# Power_Supply.net
KiCad netlist of a schematic drawn in Altium Designer
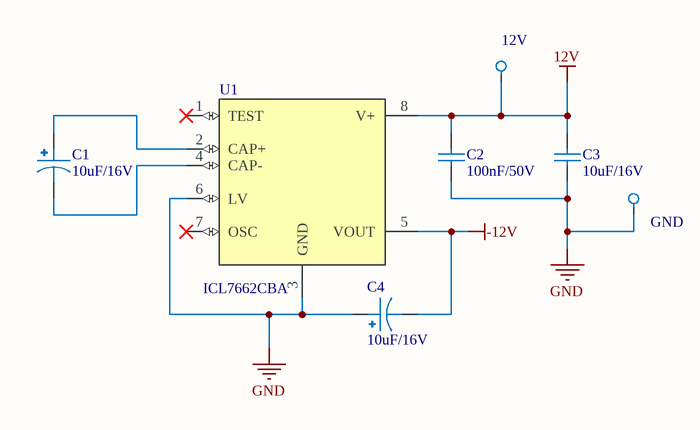
[diagram p0: Power_Supply.SchDoc]

(export (version "E")
  (design (tool "Eeschema 10.0.6"))
  (components
    (comp (ref "12V")
      (value "Testpoint_SMD")
      (footprint "TestPoint_Pad_3.0x3.0mm")
      (libsource (lib "BluetoothTracking") (part "Testpoint_SMD"))
    )
    (comp (ref "C1")
      (value "10uF/16V")
      (footprint "TanTa_Cap_A")
      (description "Tantalum Capacitors 10uF 16V 1206")
      (fields (field (name "SUPPLY PART NUMBER") "AVX"))
      (libsource (lib "") (part "Tanta_Cap_10uF_16V_1206_1"))
    )
    (comp (ref "C2")
      (value "100nF/50V")
      (footprint "CAP_0603")
      (description "CAP, size 0603, 100nF, 50V")
      (fields (field (name "SUPPLY PART NUMBER") "Tụ Gốm 0603 100nF (0.1uF) 50V"))
      (libsource (lib "BluetoothTracking") (part "Ceramic_Cap_100nF_50V_0603"))
    )
    (comp (ref "C3")
      (value "10uF/16V")
      (footprint "CAP_0603")
      (description "CAP, size 0603, 10uF, 16V")
      (fields (field (name "SUPPLY PART NUMBER") "Tụ Gốm 0603 10uF 16V"))
      (libsource (lib "BluetoothTracking") (part "Ceramic_Cap_10uF_16V_0603"))
    )
    (comp (ref "C4")
      (value "10uF/16V")
      (footprint "TanTa_Cap_A")
      (description "Tantalum Capacitors 10uF 16V 1206")
      (fields (field (name "SUPPLY PART NUMBER") "AVX"))
      (libsource (lib "BluetoothTracking") (part "Tanta_Cap_10uF_16V_1206"))
    )
    (comp (ref "GND")
      (value "Testpoint_SMD")
      (footprint "TestPoint_Pad_3.0x3.0mm")
      (libsource (lib "BluetoothTracking") (part "Testpoint_SMD"))
    )
    (comp (ref "U1")
      (value "ICL7662CBA")
      (footprint "SOIC-8")
      (description "Vin: 4.5V ~ 20V, Vout: -Vin, 8-SOIC")
      (fields (field (name "SUPPLY PART NUMBER") "IC Dán ICL7662"))
      (libsource (lib "BluetoothTracking") (part "ICL7662CBA"))
    )
  )
  (nets
    (net (code "1") (name "-12V") (class "Default")
      (node (ref "C4") (pin "2") (pinfunction "2_2") (pintype "passive"))
      (node (ref "U1") (pin "5") (pinfunction "VOUT_5") (pintype "power_in"))
    )
    (net (code "2") (name "12V") (class "Default")
      (node (ref "12V") (pin "1") (pinfunction "1_1") (pintype "passive"))
      (node (ref "C2") (pin "2") (pinfunction "2_2") (pintype "passive"))
      (node (ref "C3") (pin "2") (pinfunction "2_2") (pintype "passive"))
      (node (ref "U1") (pin "8") (pinfunction "V+_8") (pintype "power_in"))
    )
    (net (code "3") (name "GND") (class "Default")
      (node (ref "C2") (pin "1") (pinfunction "1_1") (pintype "passive"))
      (node (ref "C3") (pin "1") (pinfunction "1_1") (pintype "passive"))
      (node (ref "C4") (pin "1") (pinfunction "1_1") (pintype "passive"))
      (node (ref "GND") (pin "1") (pinfunction "1_1") (pintype "passive"))
      (node (ref "U1") (pin "3") (pinfunction "GND_3") (pintype "power_in"))
      (node (ref "U1") (pin "6") (pinfunction "LV_6") (pintype "bidirectional"))
    )
    (net (code "4") (name "Net-(U1-CAP+)") (class "Default")
      (node (ref "C1") (pin "1") (pinfunction "1_1") (pintype "passive"))
      (node (ref "U1") (pin "2") (pinfunction "CAP+_2") (pintype "bidirectional"))
    )
    (net (code "5") (name "Net-(U1-CAP-)") (class "Default")
      (node (ref "C1") (pin "2") (pinfunction "2_2") (pintype "passive"))
      (node (ref "U1") (pin "4") (pinfunction "CAP-_4") (pintype "bidirectional"))
    )
    (net (code "6") (name "unconnected-(U1-OSC-Pad7)") (class "Default")
      (node (ref "U1") (pin "7") (pinfunction "OSC_7") (pintype "bidirectional+no_connect"))
    )
    (net (code "7") (name "unconnected-(U1-TEST-Pad1)") (class "Default")
      (node (ref "U1") (pin "1") (pinfunction "TEST_1") (pintype "bidirectional+no_connect"))
    )
  )
)
